# Display.net
KiCad netlist of a schematic drawn in Altium Designer
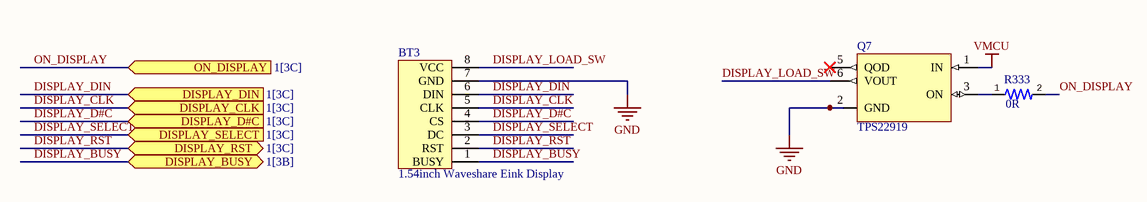
[diagram p0: Display.SchDoc]

(export (version "E")
  (design (tool "Eeschema 10.0.6"))
  (components
    (comp (ref "BT3")
      (value "1.54inch Waveshare Eink Display")
      (footprint "1.54inch waveshare eink")
      (libsource (lib "Keyboard_parts") (part "1.54inch Waveshare Eink Display"))
    )
    (comp (ref "Q7")
      (value "TPS22919")
      (footprint "TPS22919DCKR - Load SW")
      (description "Buffer/Inverter Based Peripheral Driver, 3A, PDSO6")
      (fields
        (field (name "MANUFACTURER") "Texas Instruments")
        (field (name "MANUFACTURER PART NUMBER") "TPS22919DCKT")
      )
      (libsource (lib "Keyboard_parts") (part "TPS22919"))
    )
    (comp (ref "R333")
      (value "0R")
      (footprint "Resistor 0402")
      (description "Metal Glaze/thick Film, 0.0625W, 0ohm, Surface Mount, 0402")
      (fields
        (field (name "MANUFACTURER") "Yageo")
        (field (name "MANUFACTURER PART NUMBER") "RC0402JR-070RL")
      )
      (libsource (lib "InsaneIntegratedLib") (part "RES 0R 0402"))
    )
  )
  (nets
    (net (code "1") (name "/DISPLAY_BUSY") (class "Default")
      (node (ref "BT3") (pin "1") (pinfunction "BUSY_1") (pintype "passive"))
    )
    (net (code "2") (name "/DISPLAY_CLK") (class "Default")
      (node (ref "BT3") (pin "5") (pinfunction "CLK_5") (pintype "passive"))
    )
    (net (code "3") (name "/DISPLAY_D#C") (class "Default")
      (node (ref "BT3") (pin "4") (pinfunction "CS_4") (pintype "passive"))
    )
    (net (code "4") (name "/DISPLAY_DIN") (class "Default")
      (node (ref "BT3") (pin "6") (pinfunction "DIN_6") (pintype "passive"))
    )
    (net (code "5") (name "/DISPLAY_LOAD_SW") (class "Default")
      (node (ref "BT3") (pin "8") (pinfunction "VCC_8") (pintype "passive"))
      (node (ref "Q7") (pin "6") (pinfunction "VOUT_6") (pintype "output"))
    )
    (net (code "6") (name "/DISPLAY_RST") (class "Default")
      (node (ref "BT3") (pin "2") (pinfunction "RST_2") (pintype "passive"))
    )
    (net (code "7") (name "/DISPLAY_SELECT") (class "Default")
      (node (ref "BT3") (pin "3") (pinfunction "DC_3") (pintype "passive"))
    )
    (net (code "8") (name "/ON_DISPLAY") (class "Default")
      (node (ref "R333") (pin "2") (pinfunction "2_2") (pintype "passive"))
    )
    (net (code "9") (name "GND") (class "Default")
      (node (ref "BT3") (pin "7") (pinfunction "GND_7") (pintype "passive"))
      (node (ref "Q7") (pin "2") (pinfunction "GND_2") (pintype "passive"))
    )
    (net (code "10") (name "Net-(Q7-ON)") (class "Default")
      (node (ref "Q7") (pin "3") (pinfunction "ON_3") (pintype "bidirectional"))
      (node (ref "R333") (pin "1") (pinfunction "1_1") (pintype "passive"))
    )
    (net (code "11") (name "VMCU") (class "Default")
      (node (ref "Q7") (pin "1") (pinfunction "IN_1") (pintype "input"))
    )
    (net (code "12") (name "unconnected-(Q7-QOD-Pad5)") (class "Default")
      (node (ref "Q7") (pin "5") (pinfunction "QOD_5") (pintype "output+no_connect"))
    )
  )
)
